# Sheet2.net
KiCad netlist of a schematic drawn in Altium Designer
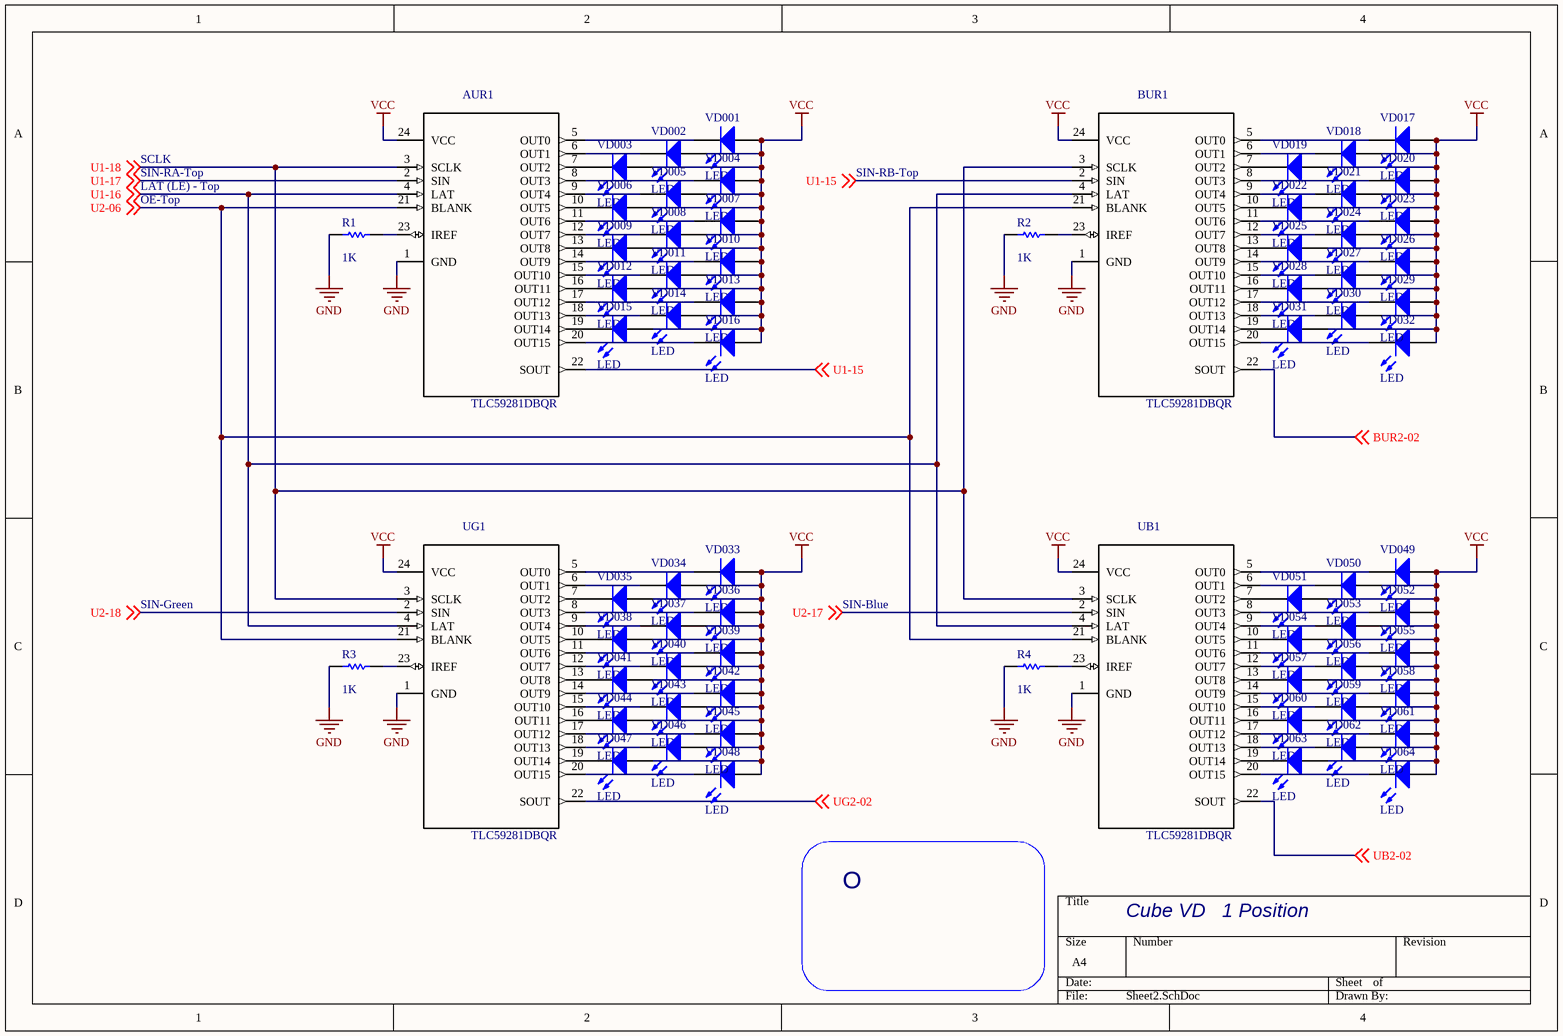
[diagram p0: Sheet2.SchDoc]

(export (version "E")
  (design (tool "Eeschema 10.0.6"))
  (components
    (comp (ref "AUR1")
      (value "TLC59281DBQR")
      (footprint "SOP63P600X175-28N")
      (description "16-Channel, Constant-Current LED Driver without LED Open Detection 24-SSOP -40 to 85")
      (fields (field (name "MF") "Texas Instruments"))
      (libsource (lib "TLC59281DBQR") (part "TLC59281DBQR"))
    )
    (comp (ref "BUR1")
      (value "TLC59281DBQR")
      (footprint "SOP63P600X175-28N")
      (description "16-Channel, Constant-Current LED Driver without LED Open Detection 24-SSOP -40 to 85")
      (fields (field (name "MF") "Texas Instruments"))
      (libsource (lib "TLC59281DBQR") (part "TLC59281DBQR"))
    )
    (comp (ref "R1")
      (value "1K")
      (footprint "AXIAL-0.3")
      (description "Resistor")
      (fields (field (name "Comment") "Res1") (field (name "PUBLISHER") "Altium Limited"))
      (libsource (lib "Miscellaneous Devices") (part "Res1"))
    )
    (comp (ref "R2")
      (value "1K")
      (footprint "AXIAL-0.3")
      (description "Resistor")
      (fields (field (name "Comment") "Res1") (field (name "PUBLISHER") "Altium Limited"))
      (libsource (lib "Miscellaneous Devices") (part "Res1"))
    )
    (comp (ref "R3")
      (value "1K")
      (footprint "AXIAL-0.3")
      (description "Resistor")
      (fields (field (name "Comment") "Res1") (field (name "PUBLISHER") "Altium Limited"))
      (libsource (lib "Miscellaneous Devices") (part "Res1"))
    )
    (comp (ref "R4")
      (value "1K")
      (footprint "AXIAL-0.3")
      (description "Resistor")
      (fields (field (name "Comment") "Res1") (field (name "PUBLISHER") "Altium Limited"))
      (libsource (lib "Miscellaneous Devices") (part "Res1"))
    )
    (comp (ref "UB1")
      (value "TLC59281DBQR")
      (footprint "SOP63P600X175-28N")
      (description "16-Channel, Constant-Current LED Driver without LED Open Detection 24-SSOP -40 to 85")
      (fields (field (name "MF") "Texas Instruments"))
      (libsource (lib "TLC59281DBQR") (part "TLC59281DBQR"))
    )
    (comp (ref "UG1")
      (value "TLC59281DBQR")
      (footprint "SOP63P600X175-28N")
      (description "16-Channel, Constant-Current LED Driver without LED Open Detection 24-SSOP -40 to 85")
      (fields (field (name "MF") "Texas Instruments"))
      (libsource (lib "TLC59281DBQR") (part "TLC59281DBQR"))
    )
    (comp (ref "VD001")
      (value "LED")
      (footprint "LED-0")
      (description "Typical INFRARED GaAs LED")
      (fields (field (name "PUBLISHER") "Altium Limited"))
      (libsource (lib "Miscellaneous Devices") (part "LED0"))
    )
    (comp (ref "VD002")
      (value "LED")
      (footprint "LED-0")
      (description "Typical INFRARED GaAs LED")
      (fields (field (name "PUBLISHER") "Altium Limited"))
      (libsource (lib "Miscellaneous Devices") (part "LED0"))
    )
    (comp (ref "VD003")
      (value "LED")
      (footprint "LED-0")
      (description "Typical INFRARED GaAs LED")
      (fields (field (name "PUBLISHER") "Altium Limited"))
      (libsource (lib "Miscellaneous Devices") (part "LED0"))
    )
    (comp (ref "VD004")
      (value "LED")
      (footprint "LED-0")
      (description "Typical INFRARED GaAs LED")
      (fields (field (name "PUBLISHER") "Altium Limited"))
      (libsource (lib "Miscellaneous Devices") (part "LED0"))
    )
    (comp (ref "VD005")
      (value "LED")
      (footprint "LED-0")
      (description "Typical INFRARED GaAs LED")
      (fields (field (name "PUBLISHER") "Altium Limited"))
      (libsource (lib "Miscellaneous Devices") (part "LED0"))
    )
    (comp (ref "VD006")
      (value "LED")
      (footprint "LED-0")
      (description "Typical INFRARED GaAs LED")
      (fields (field (name "PUBLISHER") "Altium Limited"))
      (libsource (lib "Miscellaneous Devices") (part "LED0"))
    )
    (comp (ref "VD007")
      (value "LED")
      (footprint "LED-0")
      (description "Typical INFRARED GaAs LED")
      (fields (field (name "PUBLISHER") "Altium Limited"))
      (libsource (lib "Miscellaneous Devices") (part "LED0"))
    )
    (comp (ref "VD008")
      (value "LED")
      (footprint "LED-0")
      (description "Typical INFRARED GaAs LED")
      (fields (field (name "PUBLISHER") "Altium Limited"))
      (libsource (lib "Miscellaneous Devices") (part "LED0"))
    )
    (comp (ref "VD009")
      (value "LED")
      (footprint "LED-0")
      (description "Typical INFRARED GaAs LED")
      (fields (field (name "PUBLISHER") "Altium Limited"))
      (libsource (lib "Miscellaneous Devices") (part "LED0"))
    )
    (comp (ref "VD010")
      (value "LED")
      (footprint "LED-0")
      (description "Typical INFRARED GaAs LED")
      (fields (field (name "PUBLISHER") "Altium Limited"))
      (libsource (lib "Miscellaneous Devices") (part "LED0"))
    )
    (comp (ref "VD011")
      (value "LED")
      (footprint "LED-0")
      (description "Typical INFRARED GaAs LED")
      (fields (field (name "PUBLISHER") "Altium Limited"))
      (libsource (lib "Miscellaneous Devices") (part "LED0"))
    )
    (comp (ref "VD012")
      (value "LED")
      (footprint "LED-0")
      (description "Typical INFRARED GaAs LED")
      (fields (field (name "PUBLISHER") "Altium Limited"))
      (libsource (lib "Miscellaneous Devices") (part "LED0"))
    )
    (comp (ref "VD013")
      (value "LED")
      (footprint "LED-0")
      (description "Typical INFRARED GaAs LED")
      (fields (field (name "PUBLISHER") "Altium Limited"))
      (libsource (lib "Miscellaneous Devices") (part "LED0"))
    )
    (comp (ref "VD014")
      (value "LED")
      (footprint "LED-0")
      (description "Typical INFRARED GaAs LED")
      (fields (field (name "PUBLISHER") "Altium Limited"))
      (libsource (lib "Miscellaneous Devices") (part "LED0"))
    )
    (comp (ref "VD015")
      (value "LED")
      (footprint "LED-0")
      (description "Typical INFRARED GaAs LED")
      (fields (field (name "PUBLISHER") "Altium Limited"))
      (libsource (lib "Miscellaneous Devices") (part "LED0"))
    )
    (comp (ref "VD016")
      (value "LED")
      (footprint "LED-0")
      (description "Typical INFRARED GaAs LED")
      (fields (field (name "PUBLISHER") "Altium Limited"))
      (libsource (lib "Miscellaneous Devices") (part "LED0"))
    )
    (comp (ref "VD017")
      (value "LED")
      (footprint "LED-0")
      (description "Typical INFRARED GaAs LED")
      (fields (field (name "PUBLISHER") "Altium Limited"))
      (libsource (lib "Miscellaneous Devices") (part "LED0"))
    )
    (comp (ref "VD018")
      (value "LED")
      (footprint "LED-0")
      (description "Typical INFRARED GaAs LED")
      (fields (field (name "PUBLISHER") "Altium Limited"))
      (libsource (lib "Miscellaneous Devices") (part "LED0"))
    )
    (comp (ref "VD019")
      (value "LED")
      (footprint "LED-0")
      (description "Typical INFRARED GaAs LED")
      (fields (field (name "PUBLISHER") "Altium Limited"))
      (libsource (lib "Miscellaneous Devices") (part "LED0"))
    )
    (comp (ref "VD020")
      (value "LED")
      (footprint "LED-0")
      (description "Typical INFRARED GaAs LED")
      (fields (field (name "PUBLISHER") "Altium Limited"))
      (libsource (lib "Miscellaneous Devices") (part "LED0"))
    )
    (comp (ref "VD021")
      (value "LED")
      (footprint "LED-0")
      (description "Typical INFRARED GaAs LED")
      (fields (field (name "PUBLISHER") "Altium Limited"))
      (libsource (lib "Miscellaneous Devices") (part "LED0"))
    )
    (comp (ref "VD022")
      (value "LED")
      (footprint "LED-0")
      (description "Typical INFRARED GaAs LED")
      (fields (field (name "PUBLISHER") "Altium Limited"))
      (libsource (lib "Miscellaneous Devices") (part "LED0"))
    )
    (comp (ref "VD023")
      (value "LED")
      (footprint "LED-0")
      (description "Typical INFRARED GaAs LED")
      (fields (field (name "PUBLISHER") "Altium Limited"))
      (libsource (lib "Miscellaneous Devices") (part "LED0"))
    )
    (comp (ref "VD024")
      (value "LED")
      (footprint "LED-0")
      (description "Typical INFRARED GaAs LED")
      (fields (field (name "PUBLISHER") "Altium Limited"))
      (libsource (lib "Miscellaneous Devices") (part "LED0"))
    )
    (comp (ref "VD025")
      (value "LED")
      (footprint "LED-0")
      (description "Typical INFRARED GaAs LED")
      (fields (field (name "PUBLISHER") "Altium Limited"))
      (libsource (lib "Miscellaneous Devices") (part "LED0"))
    )
    (comp (ref "VD026")
      (value "LED")
      (footprint "LED-0")
      (description "Typical INFRARED GaAs LED")
      (fields (field (name "PUBLISHER") "Altium Limited"))
      (libsource (lib "Miscellaneous Devices") (part "LED0"))
    )
    (comp (ref "VD027")
      (value "LED")
      (footprint "LED-0")
      (description "Typical INFRARED GaAs LED")
      (fields (field (name "PUBLISHER") "Altium Limited"))
      (libsource (lib "Miscellaneous Devices") (part "LED0"))
    )
    (comp (ref "VD028")
      (value "LED")
      (footprint "LED-0")
      (description "Typical INFRARED GaAs LED")
      (fields (field (name "PUBLISHER") "Altium Limited"))
      (libsource (lib "Miscellaneous Devices") (part "LED0"))
    )
    (comp (ref "VD029")
      (value "LED")
      (footprint "LED-0")
      (description "Typical INFRARED GaAs LED")
      (fields (field (name "PUBLISHER") "Altium Limited"))
      (libsource (lib "Miscellaneous Devices") (part "LED0"))
    )
    (comp (ref "VD030")
      (value "LED")
      (footprint "LED-0")
      (description "Typical INFRARED GaAs LED")
      (fields (field (name "PUBLISHER") "Altium Limited"))
      (libsource (lib "Miscellaneous Devices") (part "LED0"))
    )
    (comp (ref "VD031")
      (value "LED")
      (footprint "LED-0")
      (description "Typical INFRARED GaAs LED")
      (fields (field (name "PUBLISHER") "Altium Limited"))
      (libsource (lib "Miscellaneous Devices") (part "LED0"))
    )
    (comp (ref "VD032")
      (value "LED")
      (footprint "LED-0")
      (description "Typical INFRARED GaAs LED")
      (fields (field (name "PUBLISHER") "Altium Limited"))
      (libsource (lib "Miscellaneous Devices") (part "LED0"))
    )
    (comp (ref "VD033")
      (value "LED")
      (footprint "LED-0")
      (description "Typical INFRARED GaAs LED")
      (fields (field (name "PUBLISHER") "Altium Limited"))
      (libsource (lib "Miscellaneous Devices") (part "LED0"))
    )
    (comp (ref "VD034")
      (value "LED")
      (footprint "LED-0")
      (description "Typical INFRARED GaAs LED")
      (fields (field (name "PUBLISHER") "Altium Limited"))
      (libsource (lib "Miscellaneous Devices") (part "LED0"))
    )
    (comp (ref "VD035")
      (value "LED")
      (footprint "LED-0")
      (description "Typical INFRARED GaAs LED")
      (fields (field (name "PUBLISHER") "Altium Limited"))
      (libsource (lib "Miscellaneous Devices") (part "LED0"))
    )
    (comp (ref "VD036")
      (value "LED")
      (footprint "LED-0")
      (description "Typical INFRARED GaAs LED")
      (fields (field (name "PUBLISHER") "Altium Limited"))
      (libsource (lib "Miscellaneous Devices") (part "LED0"))
    )
    (comp (ref "VD037")
      (value "LED")
      (footprint "LED-0")
      (description "Typical INFRARED GaAs LED")
      (fields (field (name "PUBLISHER") "Altium Limited"))
      (libsource (lib "Miscellaneous Devices") (part "LED0"))
    )
    (comp (ref "VD038")
      (value "LED")
      (footprint "LED-0")
      (description "Typical INFRARED GaAs LED")
      (fields (field (name "PUBLISHER") "Altium Limited"))
      (libsource (lib "Miscellaneous Devices") (part "LED0"))
    )
    (comp (ref "VD039")
      (value "LED")
      (footprint "LED-0")
      (description "Typical INFRARED GaAs LED")
      (fields (field (name "PUBLISHER") "Altium Limited"))
      (libsource (lib "Miscellaneous Devices") (part "LED0"))
    )
    (comp (ref "VD040")
      (value "LED")
      (footprint "LED-0")
      (description "Typical INFRARED GaAs LED")
      (fields (field (name "PUBLISHER") "Altium Limited"))
      (libsource (lib "Miscellaneous Devices") (part "LED0"))
    )
    (comp (ref "VD041")
      (value "LED")
      (footprint "LED-0")
      (description "Typical INFRARED GaAs LED")
      (fields (field (name "PUBLISHER") "Altium Limited"))
      (libsource (lib "Miscellaneous Devices") (part "LED0"))
    )
    (comp (ref "VD042")
      (value "LED")
      (footprint "LED-0")
      (description "Typical INFRARED GaAs LED")
      (fields (field (name "PUBLISHER") "Altium Limited"))
      (libsource (lib "Miscellaneous Devices") (part "LED0"))
    )
    (comp (ref "VD043")
      (value "LED")
      (footprint "LED-0")
      (description "Typical INFRARED GaAs LED")
      (fields (field (name "PUBLISHER") "Altium Limited"))
      (libsource (lib "Miscellaneous Devices") (part "LED0"))
    )
    (comp (ref "VD044")
      (value "LED")
      (footprint "LED-0")
      (description "Typical INFRARED GaAs LED")
      (fields (field (name "PUBLISHER") "Altium Limited"))
      (libsource (lib "Miscellaneous Devices") (part "LED0"))
    )
    (comp (ref "VD045")
      (value "LED")
      (footprint "LED-0")
      (description "Typical INFRARED GaAs LED")
      (fields (field (name "PUBLISHER") "Altium Limited"))
      (libsource (lib "Miscellaneous Devices") (part "LED0"))
    )
    (comp (ref "VD046")
      (value "LED")
      (footprint "LED-0")
      (description "Typical INFRARED GaAs LED")
      (fields (field (name "PUBLISHER") "Altium Limited"))
      (libsource (lib "Miscellaneous Devices") (part "LED0"))
    )
    (comp (ref "VD047")
      (value "LED")
      (footprint "LED-0")
      (description "Typical INFRARED GaAs LED")
      (fields (field (name "PUBLISHER") "Altium Limited"))
      (libsource (lib "Miscellaneous Devices") (part "LED0"))
    )
    (comp (ref "VD048")
      (value "LED")
      (footprint "LED-0")
      (description "Typical INFRARED GaAs LED")
      (fields (field (name "PUBLISHER") "Altium Limited"))
      (libsource (lib "Miscellaneous Devices") (part "LED0"))
    )
    (comp (ref "VD049")
      (value "LED")
      (footprint "LED-0")
      (description "Typical INFRARED GaAs LED")
      (fields (field (name "PUBLISHER") "Altium Limited"))
      (libsource (lib "Miscellaneous Devices") (part "LED0"))
    )
    (comp (ref "VD050")
      (value "LED")
      (footprint "LED-0")
      (description "Typical INFRARED GaAs LED")
      (fields (field (name "PUBLISHER") "Altium Limited"))
      (libsource (lib "Miscellaneous Devices") (part "LED0"))
    )
    (comp (ref "VD051")
      (value "LED")
      (footprint "LED-0")
      (description "Typical INFRARED GaAs LED")
      (fields (field (name "PUBLISHER") "Altium Limited"))
      (libsource (lib "Miscellaneous Devices") (part "LED0"))
    )
    (comp (ref "VD052")
      (value "LED")
      (footprint "LED-0")
      (description "Typical INFRARED GaAs LED")
      (fields (field (name "PUBLISHER") "Altium Limited"))
      (libsource (lib "Miscellaneous Devices") (part "LED0"))
    )
    (comp (ref "VD053")
      (value "LED")
      (footprint "LED-0")
      (description "Typical INFRARED GaAs LED")
      (fields (field (name "PUBLISHER") "Altium Limited"))
      (libsource (lib "Miscellaneous Devices") (part "LED0"))
    )
    (comp (ref "VD054")
      (value "LED")
      (footprint "LED-0")
      (description "Typical INFRARED GaAs LED")
      (fields (field (name "PUBLISHER") "Altium Limited"))
      (libsource (lib "Miscellaneous Devices") (part "LED0"))
    )
    (comp (ref "VD055")
      (value "LED")
      (footprint "LED-0")
      (description "Typical INFRARED GaAs LED")
      (fields (field (name "PUBLISHER") "Altium Limited"))
      (libsource (lib "Miscellaneous Devices") (part "LED0"))
    )
    (comp (ref "VD056")
      (value "LED")
      (footprint "LED-0")
      (description "Typical INFRARED GaAs LED")
      (fields (field (name "PUBLISHER") "Altium Limited"))
      (libsource (lib "Miscellaneous Devices") (part "LED0"))
    )
    (comp (ref "VD057")
      (value "LED")
      (footprint "LED-0")
      (description "Typical INFRARED GaAs LED")
      (fields (field (name "PUBLISHER") "Altium Limited"))
      (libsource (lib "Miscellaneous Devices") (part "LED0"))
    )
    (comp (ref "VD058")
      (value "LED")
      (footprint "LED-0")
      (description "Typical INFRARED GaAs LED")
      (fields (field (name "PUBLISHER") "Altium Limited"))
      (libsource (lib "Miscellaneous Devices") (part "LED0"))
    )
    (comp (ref "VD059")
      (value "LED")
      (footprint "LED-0")
      (description "Typical INFRARED GaAs LED")
      (fields (field (name "PUBLISHER") "Altium Limited"))
      (libsource (lib "Miscellaneous Devices") (part "LED0"))
    )
    (comp (ref "VD060")
      (value "LED")
      (footprint "LED-0")
      (description "Typical INFRARED GaAs LED")
      (fields (field (name "PUBLISHER") "Altium Limited"))
      (libsource (lib "Miscellaneous Devices") (part "LED0"))
    )
    (comp (ref "VD061")
      (value "LED")
      (footprint "LED-0")
      (description "Typical INFRARED GaAs LED")
      (fields (field (name "PUBLISHER") "Altium Limited"))
      (libsource (lib "Miscellaneous Devices") (part "LED0"))
    )
    (comp (ref "VD062")
      (value "LED")
      (footprint "LED-0")
      (description "Typical INFRARED GaAs LED")
      (fields (field (name "PUBLISHER") "Altium Limited"))
      (libsource (lib "Miscellaneous Devices") (part "LED0"))
    )
    (comp (ref "VD063")
      (value "LED")
      (footprint "LED-0")
      (description "Typical INFRARED GaAs LED")
      (fields (field (name "PUBLISHER") "Altium Limited"))
      (libsource (lib "Miscellaneous Devices") (part "LED0"))
    )
    (comp (ref "VD064")
      (value "LED")
      (footprint "LED-0")
      (description "Typical INFRARED GaAs LED")
      (fields (field (name "PUBLISHER") "Altium Limited"))
      (libsource (lib "Miscellaneous Devices") (part "LED0"))
    )
  )
  (nets
    (net (code "1") (name "BUR2-02") (class "Default")
      (node (ref "BUR1") (pin "22") (pinfunction "SOUT_22") (pintype "output"))
    )
    (net (code "2") (name "GND") (class "Default")
      (node (ref "AUR1") (pin "1") (pinfunction "GND_1") (pintype "passive"))
      (node (ref "BUR1") (pin "1") (pinfunction "GND_1") (pintype "passive"))
      (node (ref "R1") (pin "1") (pinfunction "1_1") (pintype "passive"))
      (node (ref "R2") (pin "1") (pinfunction "1_1") (pintype "passive"))
      (node (ref "R3") (pin "1") (pinfunction "1_1") (pintype "passive"))
      (node (ref "R4") (pin "1") (pinfunction "1_1") (pintype "passive"))
      (node (ref "UB1") (pin "1") (pinfunction "GND_1") (pintype "passive"))
      (node (ref "UG1") (pin "1") (pinfunction "GND_1") (pintype "passive"))
    )
    (net (code "3") (name "Net-(AUR1-IREF)") (class "Default")
      (node (ref "AUR1") (pin "23") (pinfunction "IREF_23") (pintype "bidirectional"))
      (node (ref "R1") (pin "2") (pinfunction "2_2") (pintype "passive"))
    )
    (net (code "4") (name "Net-(AUR1-OUT0)") (class "Default")
      (node (ref "AUR1") (pin "5") (pinfunction "OUT0_5") (pintype "output"))
      (node (ref "VD001") (pin "2") (pinfunction "K_2") (pintype "passive"))
    )
    (net (code "5") (name "Net-(AUR1-OUT1)") (class "Default")
      (node (ref "AUR1") (pin "6") (pinfunction "OUT1_6") (pintype "output"))
      (node (ref "VD002") (pin "2") (pinfunction "K_2") (pintype "passive"))
    )
    (net (code "6") (name "Net-(AUR1-OUT2)") (class "Default")
      (node (ref "AUR1") (pin "7") (pinfunction "OUT2_7") (pintype "output"))
      (node (ref "VD003") (pin "2") (pinfunction "K_2") (pintype "passive"))
    )
    (net (code "7") (name "Net-(AUR1-OUT3)") (class "Default")
      (node (ref "AUR1") (pin "8") (pinfunction "OUT3_8") (pintype "output"))
      (node (ref "VD004") (pin "2") (pinfunction "K_2") (pintype "passive"))
    )
    (net (code "8") (name "Net-(AUR1-OUT4)") (class "Default")
      (node (ref "AUR1") (pin "9") (pinfunction "OUT4_9") (pintype "output"))
      (node (ref "VD005") (pin "2") (pinfunction "K_2") (pintype "passive"))
    )
    (net (code "9") (name "Net-(AUR1-OUT5)") (class "Default")
      (node (ref "AUR1") (pin "10") (pinfunction "OUT5_10") (pintype "output"))
      (node (ref "VD006") (pin "2") (pinfunction "K_2") (pintype "passive"))
    )
    (net (code "10") (name "Net-(AUR1-OUT6)") (class "Default")
      (node (ref "AUR1") (pin "11") (pinfunction "OUT6_11") (pintype "output"))
      (node (ref "VD007") (pin "2") (pinfunction "K_2") (pintype "passive"))
    )
    (net (code "11") (name "Net-(AUR1-OUT7)") (class "Default")
      (node (ref "AUR1") (pin "12") (pinfunction "OUT7_12") (pintype "output"))
      (node (ref "VD008") (pin "2") (pinfunction "K_2") (pintype "passive"))
    )
    (net (code "12") (name "Net-(AUR1-OUT8)") (class "Default")
      (node (ref "AUR1") (pin "13") (pinfunction "OUT8_13") (pintype "output"))
      (node (ref "VD009") (pin "2") (pinfunction "K_2") (pintype "passive"))
    )
    (net (code "13") (name "Net-(AUR1-OUT9)") (class "Default")
      (node (ref "AUR1") (pin "14") (pinfunction "OUT9_14") (pintype "output"))
      (node (ref "VD010") (pin "2") (pinfunction "K_2") (pintype "passive"))
    )
    (net (code "14") (name "Net-(AUR1-OUT10)") (class "Default")
      (node (ref "AUR1") (pin "15") (pinfunction "OUT10_15") (pintype "output"))
      (node (ref "VD011") (pin "2") (pinfunction "K_2") (pintype "passive"))
    )
    (net (code "15") (name "Net-(AUR1-OUT11)") (class "Default")
      (node (ref "AUR1") (pin "16") (pinfunction "OUT11_16") (pintype "output"))
      (node (ref "VD012") (pin "2") (pinfunction "K_2") (pintype "passive"))
    )
    (net (code "16") (name "Net-(AUR1-OUT12)") (class "Default")
      (node (ref "AUR1") (pin "17") (pinfunction "OUT12_17") (pintype "output"))
      (node (ref "VD013") (pin "2") (pinfunction "K_2") (pintype "passive"))
    )
    (net (code "17") (name "Net-(AUR1-OUT13)") (class "Default")
      (node (ref "AUR1") (pin "18") (pinfunction "OUT13_18") (pintype "output"))
      (node (ref "VD014") (pin "2") (pinfunction "K_2") (pintype "passive"))
    )
    (net (code "18") (name "Net-(AUR1-OUT14)") (class "Default")
      (node (ref "AUR1") (pin "19") (pinfunction "OUT14_19") (pintype "output"))
      (node (ref "VD015") (pin "2") (pinfunction "K_2") (pintype "passive"))
    )
    (net (code "19") (name "Net-(AUR1-OUT15)") (class "Default")
      (node (ref "AUR1") (pin "20") (pinfunction "OUT15_20") (pintype "output"))
      (node (ref "VD016") (pin "2") (pinfunction "K_2") (pintype "passive"))
    )
    (net (code "20") (name "Net-(BUR1-IREF)") (class "Default")
      (node (ref "BUR1") (pin "23") (pinfunction "IREF_23") (pintype "bidirectional"))
      (node (ref "R2") (pin "2") (pinfunction "2_2") (pintype "passive"))
    )
    (net (code "21") (name "Net-(BUR1-OUT0)") (class "Default")
      (node (ref "BUR1") (pin "5") (pinfunction "OUT0_5") (pintype "output"))
      (node (ref "VD017") (pin "2") (pinfunction "K_2") (pintype "passive"))
    )
    (net (code "22") (name "Net-(BUR1-OUT1)") (class "Default")
      (node (ref "BUR1") (pin "6") (pinfunction "OUT1_6") (pintype "output"))
      (node (ref "VD018") (pin "2") (pinfunction "K_2") (pintype "passive"))
    )
    (net (code "23") (name "Net-(BUR1-OUT2)") (class "Default")
      (node (ref "BUR1") (pin "7") (pinfunction "OUT2_7") (pintype "output"))
      (node (ref "VD019") (pin "2") (pinfunction "K_2") (pintype "passive"))
    )
    (net (code "24") (name "Net-(BUR1-OUT3)") (class "Default")
      (node (ref "BUR1") (pin "8") (pinfunction "OUT3_8") (pintype "output"))
      (node (ref "VD020") (pin "2") (pinfunction "K_2") (pintype "passive"))
    )
    (net (code "25") (name "Net-(BUR1-OUT4)") (class "Default")
      (node (ref "BUR1") (pin "9") (pinfunction "OUT4_9") (pintype "output"))
      (node (ref "VD021") (pin "2") (pinfunction "K_2") (pintype "passive"))
    )
    (net (code "26") (name "Net-(BUR1-OUT5)") (class "Default")
      (node (ref "BUR1") (pin "10") (pinfunction "OUT5_10") (pintype "output"))
      (node (ref "VD022") (pin "2") (pinfunction "K_2") (pintype "passive"))
    )
    (net (code "27") (name "Net-(BUR1-OUT6)") (class "Default")
      (node (ref "BUR1") (pin "11") (pinfunction "OUT6_11") (pintype "output"))
      (node (ref "VD023") (pin "2") (pinfunction "K_2") (pintype "passive"))
    )
    (net (code "28") (name "Net-(BUR1-OUT7)") (class "Default")
      (node (ref "BUR1") (pin "12") (pinfunction "OUT7_12") (pintype "output"))
      (node (ref "VD024") (pin "2") (pinfunction "K_2") (pintype "passive"))
    )
    (net (code "29") (name "Net-(BUR1-OUT8)") (class "Default")
      (node (ref "BUR1") (pin "13") (pinfunction "OUT8_13") (pintype "output"))
      (node (ref "VD025") (pin "2") (pinfunction "K_2") (pintype "passive"))
    )
    (net (code "30") (name "Net-(BUR1-OUT9)") (class "Default")
      (node (ref "BUR1") (pin "14") (pinfunction "OUT9_14") (pintype "output"))
      (node (ref "VD026") (pin "2") (pinfunction "K_2") (pintype "passive"))
    )
    (net (code "31") (name "Net-(BUR1-OUT10)") (class "Default")
      (node (ref "BUR1") (pin "15") (pinfunction "OUT10_15") (pintype "output"))
      (node (ref "VD027") (pin "2") (pinfunction "K_2") (pintype "passive"))
    )
    (net (code "32") (name "Net-(BUR1-OUT11)") (class "Default")
      (node (ref "BUR1") (pin "16") (pinfunction "OUT11_16") (pintype "output"))
      (node (ref "VD028") (pin "2") (pinfunction "K_2") (pintype "passive"))
    )
    (net (code "33") (name "Net-(BUR1-OUT12)") (class "Default")
      (node (ref "BUR1") (pin "17") (pinfunction "OUT12_17") (pintype "output"))
      (node (ref "VD029") (pin "2") (pinfunction "K_2") (pintype "passive"))
    )
    (net (code "34") (name "Net-(BUR1-OUT13)") (class "Default")
      (node (ref "BUR1") (pin "18") (pinfunction "OUT13_18") (pintype "output"))
      (node (ref "VD030") (pin "2") (pinfunction "K_2") (pintype "passive"))
    )
    (net (code "35") (name "Net-(BUR1-OUT14)") (class "Default")
      (node (ref "BUR1") (pin "19") (pinfunction "OUT14_19") (pintype "output"))
      (node (ref "VD031") (pin "2") (pinfunction "K_2") (pintype "passive"))
    )
    (net (code "36") (name "Net-(BUR1-OUT15)") (class "Default")
      (node (ref "BUR1") (pin "20") (pinfunction "OUT15_20") (pintype "output"))
      (node (ref "VD032") (pin "2") (pinfunction "K_2") (pintype "passive"))
    )
    (net (code "37") (name "Net-(UB1-IREF)") (class "Default")
      (node (ref "R4") (pin "2") (pinfunction "2_2") (pintype "passive"))
      (node (ref "UB1") (pin "23") (pinfunction "IREF_23") (pintype "bidirectional"))
    )
    (net (code "38") (name "Net-(UB1-OUT0)") (class "Default")
      (node (ref "UB1") (pin "5") (pinfunction "OUT0_5") (pintype "output"))
      (node (ref "VD049") (pin "2") (pinfunction "K_2") (pintype "passive"))
    )
    (net (code "39") (name "Net-(UB1-OUT1)") (class "Default")
      (node (ref "UB1") (pin "6") (pinfunction "OUT1_6") (pintype "output"))
      (node (ref "VD050") (pin "2") (pinfunction "K_2") (pintype "passive"))
    )
    (net (code "40") (name "Net-(UB1-OUT2)") (class "Default")
      (node (ref "UB1") (pin "7") (pinfunction "OUT2_7") (pintype "output"))
      (node (ref "VD051") (pin "2") (pinfunction "K_2") (pintype "passive"))
    )
    (net (code "41") (name "Net-(UB1-OUT3)") (class "Default")
      (node (ref "UB1") (pin "8") (pinfunction "OUT3_8") (pintype "output"))
      (node (ref "VD052") (pin "2") (pinfunction "K_2") (pintype "passive"))
    )
    (net (code "42") (name "Net-(UB1-OUT4)") (class "Default")
      (node (ref "UB1") (pin "9") (pinfunction "OUT4_9") (pintype "output"))
      (node (ref "VD053") (pin "2") (pinfunction "K_2") (pintype "passive"))
    )
    (net (code "43") (name "Net-(UB1-OUT5)") (class "Default")
      (node (ref "UB1") (pin "10") (pinfunction "OUT5_10") (pintype "output"))
      (node (ref "VD054") (pin "2") (pinfunction "K_2") (pintype "passive"))
    )
    (net (code "44") (name "Net-(UB1-OUT6)") (class "Default")
      (node (ref "UB1") (pin "11") (pinfunction "OUT6_11") (pintype "output"))
      (node (ref "VD055") (pin "2") (pinfunction "K_2") (pintype "passive"))
    )
    (net (code "45") (name "Net-(UB1-OUT7)") (class "Default")
      (node (ref "UB1") (pin "12") (pinfunction "OUT7_12") (pintype "output"))
      (node (ref "VD056") (pin "2") (pinfunction "K_2") (pintype "passive"))
    )
    (net (code "46") (name "Net-(UB1-OUT8)") (class "Default")
      (node (ref "UB1") (pin "13") (pinfunction "OUT8_13") (pintype "output"))
      (node (ref "VD057") (pin "2") (pinfunction "K_2") (pintype "passive"))
    )
    (net (code "47") (name "Net-(UB1-OUT9)") (class "Default")
      (node (ref "UB1") (pin "14") (pinfunction "OUT9_14") (pintype "output"))
      (node (ref "VD058") (pin "2") (pinfunction "K_2") (pintype "passive"))
    )
    (net (code "48") (name "Net-(UB1-OUT10)") (class "Default")
      (node (ref "UB1") (pin "15") (pinfunction "OUT10_15") (pintype "output"))
      (node (ref "VD059") (pin "2") (pinfunction "K_2") (pintype "passive"))
    )
    (net (code "49") (name "Net-(UB1-OUT11)") (class "Default")
      (node (ref "UB1") (pin "16") (pinfunction "OUT11_16") (pintype "output"))
      (node (ref "VD060") (pin "2") (pinfunction "K_2") (pintype "passive"))
    )
    (net (code "50") (name "Net-(UB1-OUT12)") (class "Default")
      (node (ref "UB1") (pin "17") (pinfunction "OUT12_17") (pintype "output"))
      (node (ref "VD061") (pin "2") (pinfunction "K_2") (pintype "passive"))
    )
    (net (code "51") (name "Net-(UB1-OUT13)") (class "Default")
      (node (ref "UB1") (pin "18") (pinfunction "OUT13_18") (pintype "output"))
      (node (ref "VD062") (pin "2") (pinfunction "K_2") (pintype "passive"))
    )
    (net (code "52") (name "Net-(UB1-OUT14)") (class "Default")
      (node (ref "UB1") (pin "19") (pinfunction "OUT14_19") (pintype "output"))
      (node (ref "VD063") (pin "2") (pinfunction "K_2") (pintype "passive"))
    )
    (net (code "53") (name "Net-(UB1-OUT15)") (class "Default")
      (node (ref "UB1") (pin "20") (pinfunction "OUT15_20") (pintype "output"))
      (node (ref "VD064") (pin "2") (pinfunction "K_2") (pintype "passive"))
    )
    (net (code "54") (name "Net-(UG1-IREF)") (class "Default")
      (node (ref "R3") (pin "2") (pinfunction "2_2") (pintype "passive"))
      (node (ref "UG1") (pin "23") (pinfunction "IREF_23") (pintype "bidirectional"))
    )
    (net (code "55") (name "Net-(UG1-OUT0)") (class "Default")
      (node (ref "UG1") (pin "5") (pinfunction "OUT0_5") (pintype "output"))
      (node (ref "VD033") (pin "2") (pinfunction "K_2") (pintype "passive"))
    )
    (net (code "56") (name "Net-(UG1-OUT1)") (class "Default")
      (node (ref "UG1") (pin "6") (pinfunction "OUT1_6") (pintype "output"))
      (node (ref "VD034") (pin "2") (pinfunction "K_2") (pintype "passive"))
    )
    (net (code "57") (name "Net-(UG1-OUT2)") (class "Default")
      (node (ref "UG1") (pin "7") (pinfunction "OUT2_7") (pintype "output"))
      (node (ref "VD035") (pin "2") (pinfunction "K_2") (pintype "passive"))
    )
    (net (code "58") (name "Net-(UG1-OUT3)") (class "Default")
      (node (ref "UG1") (pin "8") (pinfunction "OUT3_8") (pintype "output"))
      (node (ref "VD036") (pin "2") (pinfunction "K_2") (pintype "passive"))
    )
    (net (code "59") (name "Net-(UG1-OUT4)") (class "Default")
      (node (ref "UG1") (pin "9") (pinfunction "OUT4_9") (pintype "output"))
      (node (ref "VD037") (pin "2") (pinfunction "K_2") (pintype "passive"))
    )
    (net (code "60") (name "Net-(UG1-OUT5)") (class "Default")
      (node (ref "UG1") (pin "10") (pinfunction "OUT5_10") (pintype "output"))
      (node (ref "VD038") (pin "2") (pinfunction "K_2") (pintype "passive"))
    )
    (net (code "61") (name "Net-(UG1-OUT6)") (class "Default")
      (node (ref "UG1") (pin "11") (pinfunction "OUT6_11") (pintype "output"))
      (node (ref "VD039") (pin "2") (pinfunction "K_2") (pintype "passive"))
    )
    (net (code "62") (name "Net-(UG1-OUT7)") (class "Default")
      (node (ref "UG1") (pin "12") (pinfunction "OUT7_12") (pintype "output"))
      (node (ref "VD040") (pin "2") (pinfunction "K_2") (pintype "passive"))
    )
    (net (code "63") (name "Net-(UG1-OUT8)") (class "Default")
      (node (ref "UG1") (pin "13") (pinfunction "OUT8_13") (pintype "output"))
      (node (ref "VD041") (pin "2") (pinfunction "K_2") (pintype "passive"))
    )
    (net (code "64") (name "Net-(UG1-OUT9)") (class "Default")
      (node (ref "UG1") (pin "14") (pinfunction "OUT9_14") (pintype "output"))
      (node (ref "VD042") (pin "2") (pinfunction "K_2") (pintype "passive"))
    )
    (net (code "65") (name "Net-(UG1-OUT10)") (class "Default")
      (node (ref "UG1") (pin "15") (pinfunction "OUT10_15") (pintype "output"))
      (node (ref "VD043") (pin "2") (pinfunction "K_2") (pintype "passive"))
    )
    (net (code "66") (name "Net-(UG1-OUT11)") (class "Default")
      (node (ref "UG1") (pin "16") (pinfunction "OUT11_16") (pintype "output"))
      (node (ref "VD044") (pin "2") (pinfunction "K_2") (pintype "passive"))
    )
    (net (code "67") (name "Net-(UG1-OUT12)") (class "Default")
      (node (ref "UG1") (pin "17") (pinfunction "OUT12_17") (pintype "output"))
      (node (ref "VD045") (pin "2") (pinfunction "K_2") (pintype "passive"))
    )
    (net (code "68") (name "Net-(UG1-OUT13)") (class "Default")
      (node (ref "UG1") (pin "18") (pinfunction "OUT13_18") (pintype "output"))
      (node (ref "VD046") (pin "2") (pinfunction "K_2") (pintype "passive"))
    )
    (net (code "69") (name "Net-(UG1-OUT14)") (class "Default")
      (node (ref "UG1") (pin "19") (pinfunction "OUT14_19") (pintype "output"))
      (node (ref "VD047") (pin "2") (pinfunction "K_2") (pintype "passive"))
    )
    (net (code "70") (name "Net-(UG1-OUT15)") (class "Default")
      (node (ref "UG1") (pin "20") (pinfunction "OUT15_20") (pintype "output"))
      (node (ref "VD048") (pin "2") (pinfunction "K_2") (pintype "passive"))
    )
    (net (code "71") (name "U1-15") (class "Default")
      (node (ref "AUR1") (pin "22") (pinfunction "SOUT_22") (pintype "output"))
      (node (ref "BUR1") (pin "2") (pinfunction "SIN_2") (pintype "input"))
    )
    (net (code "72") (name "U1-16") (class "Default")
      (node (ref "AUR1") (pin "4") (pinfunction "LAT_4") (pintype "input"))
      (node (ref "BUR1") (pin "4") (pinfunction "LAT_4") (pintype "input"))
      (node (ref "UB1") (pin "4") (pinfunction "LAT_4") (pintype "input"))
      (node (ref "UG1") (pin "4") (pinfunction "LAT_4") (pintype "input"))
    )
    (net (code "73") (name "U1-17") (class "Default")
      (node (ref "AUR1") (pin "2") (pinfunction "SIN_2") (pintype "input"))
    )
    (net (code "74") (name "U1-18") (class "Default")
      (node (ref "AUR1") (pin "3") (pinfunction "SCLK_3") (pintype "input"))
      (node (ref "BUR1") (pin "3") (pinfunction "SCLK_3") (pintype "input"))
      (node (ref "UB1") (pin "3") (pinfunction "SCLK_3") (pintype "input"))
      (node (ref "UG1") (pin "3") (pinfunction "SCLK_3") (pintype "input"))
    )
    (net (code "75") (name "U2-06") (class "Default")
      (node (ref "AUR1") (pin "21") (pinfunction "BLANK_21") (pintype "input"))
      (node (ref "BUR1") (pin "21") (pinfunction "BLANK_21") (pintype "input"))
      (node (ref "UB1") (pin "21") (pinfunction "BLANK_21") (pintype "input"))
      (node (ref "UG1") (pin "21") (pinfunction "BLANK_21") (pintype "input"))
    )
    (net (code "76") (name "U2-17") (class "Default")
      (node (ref "UB1") (pin "2") (pinfunction "SIN_2") (pintype "input"))
    )
    (net (code "77") (name "U2-18") (class "Default")
      (node (ref "UG1") (pin "2") (pinfunction "SIN_2") (pintype "input"))
    )
    (net (code "78") (name "UB2-02") (class "Default")
      (node (ref "UB1") (pin "22") (pinfunction "SOUT_22") (pintype "output"))
    )
    (net (code "79") (name "UG2-02") (class "Default")
      (node (ref "UG1") (pin "22") (pinfunction "SOUT_22") (pintype "output"))
    )
    (net (code "80") (name "VCC") (class "Default")
      (node (ref "AUR1") (pin "24") (pinfunction "VCC_24") (pintype "power_in"))
      (node (ref "BUR1") (pin "24") (pinfunction "VCC_24") (pintype "power_in"))
      (node (ref "UB1") (pin "24") (pinfunction "VCC_24") (pintype "power_in"))
      (node (ref "UG1") (pin "24") (pinfunction "VCC_24") (pintype "power_in"))
      (node (ref "VD001") (pin "1") (pinfunction "A_1") (pintype "passive"))
      (node (ref "VD002") (pin "1") (pinfunction "A_1") (pintype "passive"))
      (node (ref "VD003") (pin "1") (pinfunction "A_1") (pintype "passive"))
      (node (ref "VD004") (pin "1") (pinfunction "A_1") (pintype "passive"))
      (node (ref "VD005") (pin "1") (pinfunction "A_1") (pintype "passive"))
      (node (ref "VD006") (pin "1") (pinfunction "A_1") (pintype "passive"))
      (node (ref "VD007") (pin "1") (pinfunction "A_1") (pintype "passive"))
      (node (ref "VD008") (pin "1") (pinfunction "A_1") (pintype "passive"))
      (node (ref "VD009") (pin "1") (pinfunction "A_1") (pintype "passive"))
      (node (ref "VD010") (pin "1") (pinfunction "A_1") (pintype "passive"))
      (node (ref "VD011") (pin "1") (pinfunction "A_1") (pintype "passive"))
      (node (ref "VD012") (pin "1") (pinfunction "A_1") (pintype "passive"))
      (node (ref "VD013") (pin "1") (pinfunction "A_1") (pintype "passive"))
      (node (ref "VD014") (pin "1") (pinfunction "A_1") (pintype "passive"))
      (node (ref "VD015") (pin "1") (pinfunction "A_1") (pintype "passive"))
      (node (ref "VD016") (pin "1") (pinfunction "A_1") (pintype "passive"))
      (node (ref "VD017") (pin "1") (pinfunction "A_1") (pintype "passive"))
      (node (ref "VD018") (pin "1") (pinfunction "A_1") (pintype "passive"))
      (node (ref "VD019") (pin "1") (pinfunction "A_1") (pintype "passive"))
      (node (ref "VD020") (pin "1") (pinfunction "A_1") (pintype "passive"))
      (node (ref "VD021") (pin "1") (pinfunction "A_1") (pintype "passive"))
      (node (ref "VD022") (pin "1") (pinfunction "A_1") (pintype "passive"))
      (node (ref "VD023") (pin "1") (pinfunction "A_1") (pintype "passive"))
      (node (ref "VD024") (pin "1") (pinfunction "A_1") (pintype "passive"))
      (node (ref "VD025") (pin "1") (pinfunction "A_1") (pintype "passive"))
      (node (ref "VD026") (pin "1") (pinfunction "A_1") (pintype "passive"))
      (node (ref "VD027") (pin "1") (pinfunction "A_1") (pintype "passive"))
      (node (ref "VD028") (pin "1") (pinfunction "A_1") (pintype "passive"))
      (node (ref "VD029") (pin "1") (pinfunction "A_1") (pintype "passive"))
      (node (ref "VD030") (pin "1") (pinfunction "A_1") (pintype "passive"))
      (node (ref "VD031") (pin "1") (pinfunction "A_1") (pintype "passive"))
      (node (ref "VD032") (pin "1") (pinfunction "A_1") (pintype "passive"))
      (node (ref "VD033") (pin "1") (pinfunction "A_1") (pintype "passive"))
      (node (ref "VD034") (pin "1") (pinfunction "A_1") (pintype "passive"))
      (node (ref "VD035") (pin "1") (pinfunction "A_1") (pintype "passive"))
      (node (ref "VD036") (pin "1") (pinfunction "A_1") (pintype "passive"))
      (node (ref "VD037") (pin "1") (pinfunction "A_1") (pintype "passive"))
      (node (ref "VD038") (pin "1") (pinfunction "A_1") (pintype "passive"))
      (node (ref "VD039") (pin "1") (pinfunction "A_1") (pintype "passive"))
      (node (ref "VD040") (pin "1") (pinfunction "A_1") (pintype "passive"))
      (node (ref "VD041") (pin "1") (pinfunction "A_1") (pintype "passive"))
      (node (ref "VD042") (pin "1") (pinfunction "A_1") (pintype "passive"))
      (node (ref "VD043") (pin "1") (pinfunction "A_1") (pintype "passive"))
      (node (ref "VD044") (pin "1") (pinfunction "A_1") (pintype "passive"))
      (node (ref "VD045") (pin "1") (pinfunction "A_1") (pintype "passive"))
      (node (ref "VD046") (pin "1") (pinfunction "A_1") (pintype "passive"))
      (node (ref "VD047") (pin "1") (pinfunction "A_1") (pintype "passive"))
      (node (ref "VD048") (pin "1") (pinfunction "A_1") (pintype "passive"))
      (node (ref "VD049") (pin "1") (pinfunction "A_1") (pintype "passive"))
      (node (ref "VD050") (pin "1") (pinfunction "A_1") (pintype "passive"))
      (node (ref "VD051") (pin "1") (pinfunction "A_1") (pintype "passive"))
      (node (ref "VD052") (pin "1") (pinfunction "A_1") (pintype "passive"))
      (node (ref "VD053") (pin "1") (pinfunction "A_1") (pintype "passive"))
      (node (ref "VD054") (pin "1") (pinfunction "A_1") (pintype "passive"))
      (node (ref "VD055") (pin "1") (pinfunction "A_1") (pintype "passive"))
      (node (ref "VD056") (pin "1") (pinfunction "A_1") (pintype "passive"))
      (node (ref "VD057") (pin "1") (pinfunction "A_1") (pintype "passive"))
      (node (ref "VD058") (pin "1") (pinfunction "A_1") (pintype "passive"))
      (node (ref "VD059") (pin "1") (pinfunction "A_1") (pintype "passive"))
      (node (ref "VD060") (pin "1") (pinfunction "A_1") (pintype "passive"))
      (node (ref "VD061") (pin "1") (pinfunction "A_1") (pintype "passive"))
      (node (ref "VD062") (pin "1") (pinfunction "A_1") (pintype "passive"))
      (node (ref "VD063") (pin "1") (pinfunction "A_1") (pintype "passive"))
      (node (ref "VD064") (pin "1") (pinfunction "A_1") (pintype "passive"))
    )
  )
)
